# avr_adapter.net
KiCad netlist of a schematic drawn in EAGLE
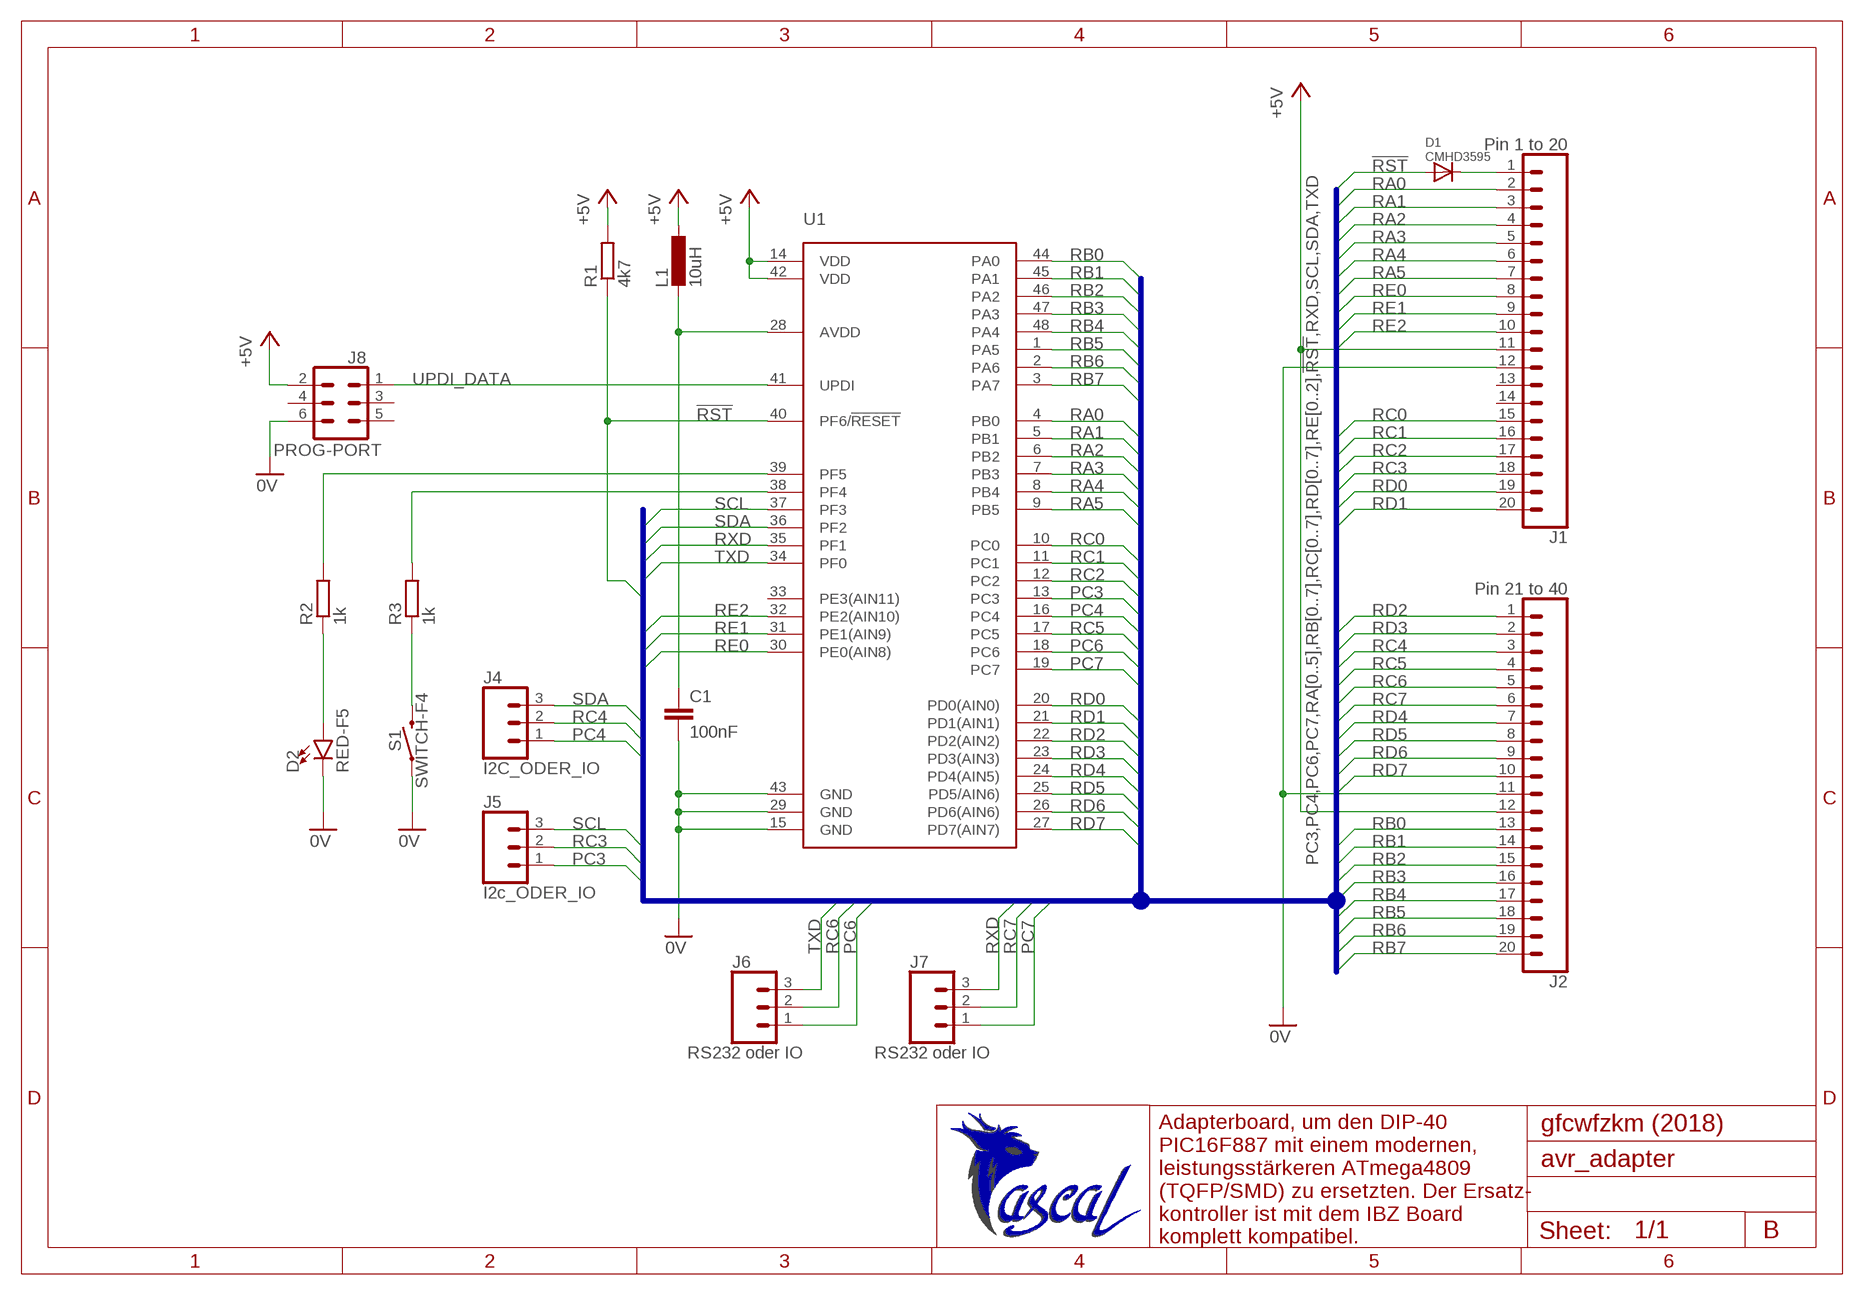
[diagram p0: schematic, sheet 1]

(export (version "E")
  (design (tool "Eeschema 10.0.6"))
  (components
    (comp (ref "C1")
      (value "100nF")
      (footprint "eagle-import:C0805")
      (libsource (lib "eagle-import") (part "C-EUC0805"))
    )
    (comp (ref "D1")
      (value "CMHD3595")
      (footprint "eagle-import:SOD-123")
      (libsource (lib "eagle-import") (part "DIODESOD-123"))
    )
    (comp (ref "D2")
      (value "RED-F5")
      (footprint "eagle-import:FKIT-LED-1206")
      (libsource (lib "eagle-import") (part "LED-FKIT-1206"))
    )
    (comp (ref "J1")
      (value "Pin 1 to 20")
      (footprint "eagle-import:1X20")
      (libsource (lib "eagle-import") (part "CONN_20"))
    )
    (comp (ref "J2")
      (value "Pin 21 to 40")
      (footprint "eagle-import:1X20")
      (libsource (lib "eagle-import") (part "CONN_20"))
    )
    (comp (ref "J4")
      (value "I2C_ODER_IO")
      (footprint "eagle-import:1X03")
      (libsource (lib "eagle-import") (part "CONN_03"))
    )
    (comp (ref "J5")
      (value "I2c_ODER_IO")
      (footprint "eagle-import:1X03")
      (libsource (lib "eagle-import") (part "CONN_03"))
    )
    (comp (ref "J6")
      (value "RS232 oder IO")
      (footprint "eagle-import:1X03")
      (libsource (lib "eagle-import") (part "CONN_03"))
    )
    (comp (ref "J7")
      (value "RS232 oder IO")
      (footprint "eagle-import:1X03")
      (libsource (lib "eagle-import") (part "CONN_03"))
    )
    (comp (ref "J8")
      (value "PROG-PORT")
      (footprint "eagle-import:2X3")
      (libsource (lib "eagle-import") (part "CONN_03X2FEMALE"))
    )
    (comp (ref "L1")
      (value "10uH")
      (footprint "eagle-import:L2012C")
      (libsource (lib "eagle-import") (part "L-EUL2012C"))
    )
    (comp (ref "R1")
      (value "4k7")
      (footprint "eagle-import:R0805")
      (libsource (lib "eagle-import") (part "R-EU_R0805"))
    )
    (comp (ref "R2")
      (value "1k")
      (footprint "eagle-import:R0805")
      (libsource (lib "eagle-import") (part "R-EU_R0805"))
    )
    (comp (ref "R3")
      (value "1k")
      (footprint "eagle-import:R0805")
      (libsource (lib "eagle-import") (part "R-EU_R0805"))
    )
    (comp (ref "S1")
      (value "SWITCH-F4")
      (footprint "eagle-import:TACTILE_SWITCH_SMD_6.0X3.5MM")
      (libsource (lib "eagle-import") (part "MOMENTARY-SWITCH-SPST-SMD-6.0X3.5MM"))
    )
    (comp (ref "U$1")
      (value "LOGO_PASCAL_GESELLEMPTY")
      (footprint "eagle-import:EMPTY")
      (libsource (lib "eagle-import") (part "LOGO_PASCAL_GESELLEMPTY"))
    )
    (comp (ref "U1")
      (value "ATMEGA4809ATMEGA4809_TQFP48")
      (footprint "eagle-import:TQFP-48")
      (libsource (lib "eagle-import") (part "ATMEGA4809ATMEGA4809_TQFP48"))
    )
  )
  (nets
    (net (code "1") (name "+5V") (class "Default")
      (node (ref "J1") (pin "11") (pinfunction "11_11") (pintype "passive"))
      (node (ref "J2") (pin "12") (pinfunction "12_12") (pintype "passive"))
      (node (ref "J8") (pin "2") (pinfunction "2_2") (pintype "bidirectional"))
      (node (ref "L1") (pin "1") (pinfunction "1_1") (pintype "passive"))
      (node (ref "R1") (pin "2") (pinfunction "2_2") (pintype "passive"))
      (node (ref "U1") (pin "14") (pinfunction "VDD_14") (pintype "bidirectional"))
      (node (ref "U1") (pin "42") (pinfunction "VDD_42") (pintype "bidirectional"))
    )
    (net (code "2") (name "/PC3") (class "Default")
      (node (ref "J5") (pin "1") (pinfunction "1_1") (pintype "passive"))
      (node (ref "U1") (pin "13") (pinfunction "PC3_13") (pintype "bidirectional"))
    )
    (net (code "3") (name "/PC4") (class "Default")
      (node (ref "J4") (pin "1") (pinfunction "1_1") (pintype "passive"))
      (node (ref "U1") (pin "16") (pinfunction "PC4_16") (pintype "bidirectional"))
    )
    (net (code "4") (name "/PC6") (class "Default")
      (node (ref "J6") (pin "1") (pinfunction "1_1") (pintype "passive"))
      (node (ref "U1") (pin "18") (pinfunction "PC6_18") (pintype "bidirectional"))
    )
    (net (code "5") (name "/PC7") (class "Default")
      (node (ref "J7") (pin "1") (pinfunction "1_1") (pintype "passive"))
      (node (ref "U1") (pin "19") (pinfunction "PC7_19") (pintype "bidirectional"))
    )
    (net (code "6") (name "/RA0") (class "Default")
      (node (ref "J1") (pin "2") (pinfunction "2_2") (pintype "passive"))
      (node (ref "U1") (pin "4") (pinfunction "PB0_4") (pintype "bidirectional"))
    )
    (net (code "7") (name "/RA1") (class "Default")
      (node (ref "J1") (pin "3") (pinfunction "3_3") (pintype "passive"))
      (node (ref "U1") (pin "5") (pinfunction "PB1_5") (pintype "bidirectional"))
    )
    (net (code "8") (name "/RA2") (class "Default")
      (node (ref "J1") (pin "4") (pinfunction "4_4") (pintype "passive"))
      (node (ref "U1") (pin "6") (pinfunction "PB2_6") (pintype "bidirectional"))
    )
    (net (code "9") (name "/RA3") (class "Default")
      (node (ref "J1") (pin "5") (pinfunction "5_5") (pintype "passive"))
      (node (ref "U1") (pin "7") (pinfunction "PB3_7") (pintype "bidirectional"))
    )
    (net (code "10") (name "/RA4") (class "Default")
      (node (ref "J1") (pin "6") (pinfunction "6_6") (pintype "passive"))
      (node (ref "U1") (pin "8") (pinfunction "PB4_8") (pintype "bidirectional"))
    )
    (net (code "11") (name "/RA5") (class "Default")
      (node (ref "J1") (pin "7") (pinfunction "7_7") (pintype "passive"))
      (node (ref "U1") (pin "9") (pinfunction "PB5_9") (pintype "bidirectional"))
    )
    (net (code "12") (name "/RB0") (class "Default")
      (node (ref "J2") (pin "13") (pinfunction "13_13") (pintype "passive"))
      (node (ref "U1") (pin "44") (pinfunction "PA0_44") (pintype "bidirectional"))
    )
    (net (code "13") (name "/RB1") (class "Default")
      (node (ref "J2") (pin "14") (pinfunction "14_14") (pintype "passive"))
      (node (ref "U1") (pin "45") (pinfunction "PA1_45") (pintype "bidirectional"))
    )
    (net (code "14") (name "/RB2") (class "Default")
      (node (ref "J2") (pin "15") (pinfunction "15_15") (pintype "passive"))
      (node (ref "U1") (pin "46") (pinfunction "PA2_46") (pintype "bidirectional"))
    )
    (net (code "15") (name "/RB3") (class "Default")
      (node (ref "J2") (pin "16") (pinfunction "16_16") (pintype "passive"))
      (node (ref "U1") (pin "47") (pinfunction "PA3_47") (pintype "bidirectional"))
    )
    (net (code "16") (name "/RB4") (class "Default")
      (node (ref "J2") (pin "17") (pinfunction "17_17") (pintype "passive"))
      (node (ref "U1") (pin "48") (pinfunction "PA4_48") (pintype "bidirectional"))
    )
    (net (code "17") (name "/RB5") (class "Default")
      (node (ref "J2") (pin "18") (pinfunction "18_18") (pintype "passive"))
      (node (ref "U1") (pin "1") (pinfunction "PA5_1") (pintype "bidirectional"))
    )
    (net (code "18") (name "/RB6") (class "Default")
      (node (ref "J2") (pin "19") (pinfunction "19_19") (pintype "passive"))
      (node (ref "U1") (pin "2") (pinfunction "PA6_2") (pintype "bidirectional"))
    )
    (net (code "19") (name "/RB7") (class "Default")
      (node (ref "J2") (pin "20") (pinfunction "20_20") (pintype "passive"))
      (node (ref "U1") (pin "3") (pinfunction "PA7_3") (pintype "bidirectional"))
    )
    (net (code "20") (name "/RC0") (class "Default")
      (node (ref "J1") (pin "15") (pinfunction "15_15") (pintype "passive"))
      (node (ref "U1") (pin "10") (pinfunction "PC0_10") (pintype "bidirectional"))
    )
    (net (code "21") (name "/RC1") (class "Default")
      (node (ref "J1") (pin "16") (pinfunction "16_16") (pintype "passive"))
      (node (ref "U1") (pin "11") (pinfunction "PC1_11") (pintype "bidirectional"))
    )
    (net (code "22") (name "/RC2") (class "Default")
      (node (ref "J1") (pin "17") (pinfunction "17_17") (pintype "passive"))
      (node (ref "U1") (pin "12") (pinfunction "PC2_12") (pintype "bidirectional"))
    )
    (net (code "23") (name "/RC3") (class "Default")
      (node (ref "J1") (pin "18") (pinfunction "18_18") (pintype "passive"))
      (node (ref "J5") (pin "2") (pinfunction "2_2") (pintype "passive"))
    )
    (net (code "24") (name "/RC4") (class "Default")
      (node (ref "J2") (pin "3") (pinfunction "3_3") (pintype "passive"))
      (node (ref "J4") (pin "2") (pinfunction "2_2") (pintype "passive"))
    )
    (net (code "25") (name "/RC5") (class "Default")
      (node (ref "J2") (pin "4") (pinfunction "4_4") (pintype "passive"))
      (node (ref "U1") (pin "17") (pinfunction "PC5_17") (pintype "bidirectional"))
    )
    (net (code "26") (name "/RC6") (class "Default")
      (node (ref "J2") (pin "5") (pinfunction "5_5") (pintype "passive"))
      (node (ref "J6") (pin "2") (pinfunction "2_2") (pintype "passive"))
    )
    (net (code "27") (name "/RC7") (class "Default")
      (node (ref "J2") (pin "6") (pinfunction "6_6") (pintype "passive"))
      (node (ref "J7") (pin "2") (pinfunction "2_2") (pintype "passive"))
    )
    (net (code "28") (name "/RD0") (class "Default")
      (node (ref "J1") (pin "19") (pinfunction "19_19") (pintype "passive"))
      (node (ref "U1") (pin "20") (pinfunction "PD0(AIN0)_20") (pintype "bidirectional"))
    )
    (net (code "29") (name "/RD1") (class "Default")
      (node (ref "J1") (pin "20") (pinfunction "20_20") (pintype "passive"))
      (node (ref "U1") (pin "21") (pinfunction "PD1(AIN1)_21") (pintype "bidirectional"))
    )
    (net (code "30") (name "/RD2") (class "Default")
      (node (ref "J2") (pin "1") (pinfunction "1_1") (pintype "passive"))
      (node (ref "U1") (pin "22") (pinfunction "PD2(AIN2)_22") (pintype "bidirectional"))
    )
    (net (code "31") (name "/RD3") (class "Default")
      (node (ref "J2") (pin "2") (pinfunction "2_2") (pintype "passive"))
      (node (ref "U1") (pin "23") (pinfunction "PD3(AIN3)_23") (pintype "bidirectional"))
    )
    (net (code "32") (name "/RD4") (class "Default")
      (node (ref "J2") (pin "7") (pinfunction "7_7") (pintype "passive"))
      (node (ref "U1") (pin "24") (pinfunction "PD4(AIN5)_24") (pintype "bidirectional"))
    )
    (net (code "33") (name "/RD5") (class "Default")
      (node (ref "J2") (pin "8") (pinfunction "8_8") (pintype "passive"))
      (node (ref "U1") (pin "25") (pinfunction "PD5/AIN6)_25") (pintype "bidirectional"))
    )
    (net (code "34") (name "/RD6") (class "Default")
      (node (ref "J2") (pin "9") (pinfunction "9_9") (pintype "passive"))
      (node (ref "U1") (pin "26") (pinfunction "PD6(AIN6)_26") (pintype "bidirectional"))
    )
    (net (code "35") (name "/RD7") (class "Default")
      (node (ref "J2") (pin "10") (pinfunction "10_10") (pintype "passive"))
      (node (ref "U1") (pin "27") (pinfunction "PD7(AIN7)_27") (pintype "bidirectional"))
    )
    (net (code "36") (name "/RE0") (class "Default")
      (node (ref "J1") (pin "8") (pinfunction "8_8") (pintype "passive"))
      (node (ref "U1") (pin "30") (pinfunction "PE0(AIN8)_30") (pintype "bidirectional"))
    )
    (net (code "37") (name "/RE1") (class "Default")
      (node (ref "J1") (pin "9") (pinfunction "9_9") (pintype "passive"))
      (node (ref "U1") (pin "31") (pinfunction "PE1(AIN9)_31") (pintype "bidirectional"))
    )
    (net (code "38") (name "/RE2") (class "Default")
      (node (ref "J1") (pin "10") (pinfunction "10_10") (pintype "passive"))
      (node (ref "U1") (pin "32") (pinfunction "PE2(AIN10)_32") (pintype "bidirectional"))
    )
    (net (code "39") (name "/RXD") (class "Default")
      (node (ref "J7") (pin "3") (pinfunction "3_3") (pintype "passive"))
      (node (ref "U1") (pin "35") (pinfunction "PF1_35") (pintype "bidirectional"))
    )
    (net (code "40") (name "/SCL") (class "Default")
      (node (ref "J5") (pin "3") (pinfunction "3_3") (pintype "passive"))
      (node (ref "U1") (pin "37") (pinfunction "PF3_37") (pintype "bidirectional"))
    )
    (net (code "41") (name "/SDA") (class "Default")
      (node (ref "J4") (pin "3") (pinfunction "3_3") (pintype "passive"))
      (node (ref "U1") (pin "36") (pinfunction "PF2_36") (pintype "bidirectional"))
    )
    (net (code "42") (name "/TXD") (class "Default")
      (node (ref "J6") (pin "3") (pinfunction "3_3") (pintype "passive"))
      (node (ref "U1") (pin "34") (pinfunction "PF0_34") (pintype "bidirectional"))
    )
    (net (code "43") (name "/UPDI_DATA") (class "Default")
      (node (ref "J8") (pin "1") (pinfunction "1_1") (pintype "bidirectional"))
      (node (ref "U1") (pin "41") (pinfunction "UPDI_41") (pintype "bidirectional"))
    )
    (net (code "45") (name "/~{RST}") (class "Default")
      (node (ref "D1") (pin "A") (pinfunction "A_A") (pintype "passive"))
      (node (ref "R1") (pin "1") (pinfunction "1_1") (pintype "passive"))
      (node (ref "U1") (pin "40") (pinfunction "PF6/~{RESET}_40") (pintype "bidirectional"))
    )
    (net (code "46") (name "0V") (class "Default")
      (node (ref "C1") (pin "2") (pinfunction "2_2") (pintype "passive"))
      (node (ref "D2") (pin "C") (pinfunction "C_C") (pintype "passive"))
      (node (ref "J1") (pin "12") (pinfunction "12_12") (pintype "passive"))
      (node (ref "J2") (pin "11") (pinfunction "11_11") (pintype "passive"))
      (node (ref "J8") (pin "6") (pinfunction "6_6") (pintype "bidirectional"))
      (node (ref "S1") (pin "1") (pinfunction "1_1") (pintype "passive"))
      (node (ref "U1") (pin "15") (pinfunction "GND_15") (pintype "bidirectional"))
      (node (ref "U1") (pin "29") (pinfunction "GND_29") (pintype "bidirectional"))
      (node (ref "U1") (pin "43") (pinfunction "GND_43") (pintype "bidirectional"))
    )
    (net (code "47") (name "Net-(D1-PadC)") (class "Default")
      (node (ref "D1") (pin "C") (pinfunction "C_C") (pintype "passive"))
      (node (ref "J1") (pin "1") (pinfunction "1_1") (pintype "passive"))
    )
    (net (code "48") (name "Net-(D2-PadA)") (class "Default")
      (node (ref "D2") (pin "A") (pinfunction "A_A") (pintype "passive"))
      (node (ref "R2") (pin "1") (pinfunction "1_1") (pintype "passive"))
    )
    (net (code "49") (name "Net-(R3-Pad1)") (class "Default")
      (node (ref "R3") (pin "1") (pinfunction "1_1") (pintype "passive"))
      (node (ref "S1") (pin "2") (pinfunction "2_2") (pintype "passive"))
    )
    (net (code "50") (name "Net-(U1-AVDD)") (class "Default")
      (node (ref "C1") (pin "1") (pinfunction "1_1") (pintype "passive"))
      (node (ref "L1") (pin "2") (pinfunction "2_2") (pintype "passive"))
      (node (ref "U1") (pin "28") (pinfunction "AVDD_28") (pintype "bidirectional"))
    )
    (net (code "51") (name "Net-(U1-PF4)") (class "Default")
      (node (ref "R3") (pin "2") (pinfunction "2_2") (pintype "passive"))
      (node (ref "U1") (pin "38") (pinfunction "PF4_38") (pintype "bidirectional"))
    )
    (net (code "52") (name "Net-(U1-PF5)") (class "Default")
      (node (ref "R2") (pin "2") (pinfunction "2_2") (pintype "passive"))
      (node (ref "U1") (pin "39") (pinfunction "PF5_39") (pintype "bidirectional"))
    )
    (net (code "53") (name "unconnected-(J1-Pad13)") (class "Default")
      (node (ref "J1") (pin "13") (pinfunction "13_13") (pintype "passive"))
    )
    (net (code "54") (name "unconnected-(J1-Pad14)") (class "Default")
      (node (ref "J1") (pin "14") (pinfunction "14_14") (pintype "passive"))
    )
    (net (code "55") (name "unconnected-(J8-Pad3)") (class "Default")
      (node (ref "J8") (pin "3") (pinfunction "3_3") (pintype "bidirectional"))
    )
    (net (code "56") (name "unconnected-(J8-Pad4)") (class "Default")
      (node (ref "J8") (pin "4") (pinfunction "4_4") (pintype "bidirectional"))
    )
    (net (code "57") (name "unconnected-(J8-Pad5)") (class "Default")
      (node (ref "J8") (pin "5") (pinfunction "5_5") (pintype "bidirectional"))
    )
    (net (code "58") (name "unconnected-(U1-PE3(AIN11)-Pad33)") (class "Default")
      (node (ref "U1") (pin "33") (pinfunction "PE3(AIN11)_33") (pintype "bidirectional"))
    )
  )
)
